# DPPXHK_SENSOR.net
KiCad netlist of a schematic drawn in Altium Designer
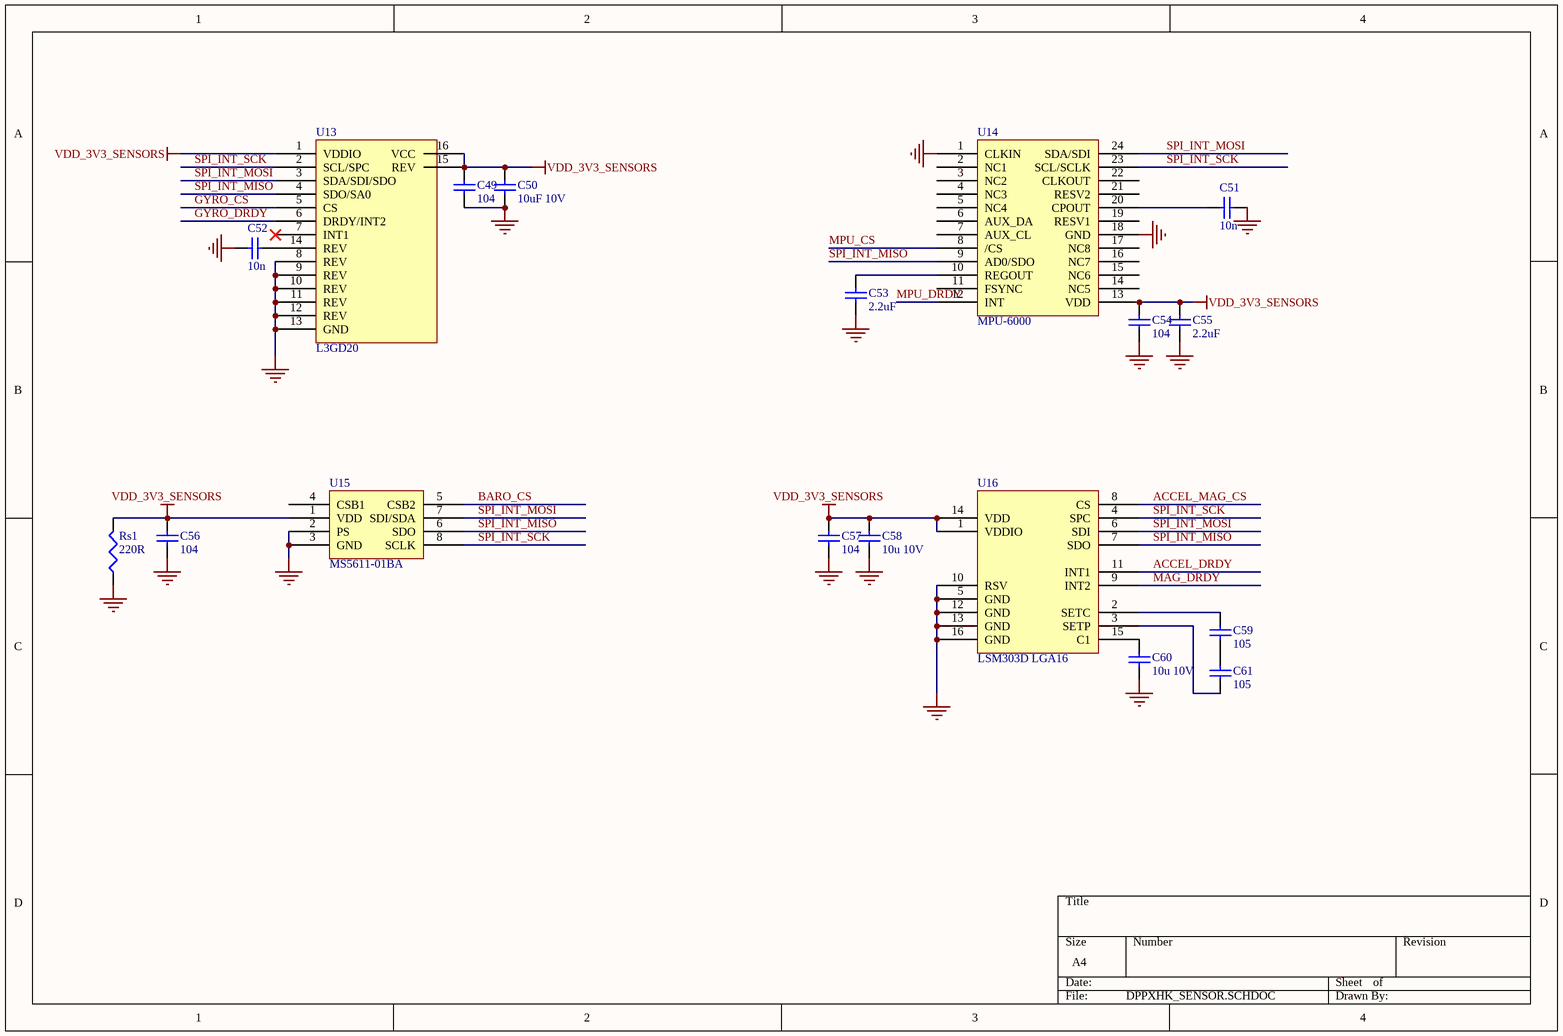
[diagram p0: DPPXHK_SENSOR.SCHDOC]

(export (version "E")
  (design (tool "Eeschema 10.0.6"))
  (components
    (comp (ref "C49")
      (value "104")
      (footprint "LC0402")
      (description "Capacitor (Semiconductor SIM Model)")
      (fields (field (name "PUBLISHER") "Altium Limited"))
      (libsource (lib "Miscellaneous Devices") (part "Cap Semi"))
    )
    (comp (ref "C50")
      (value "10uF 10V")
      (footprint "LC0402")
      (description "Capacitor (Semiconductor SIM Model)")
      (fields (field (name "PUBLISHER") "Altium Limited"))
      (libsource (lib "Miscellaneous Devices") (part "Cap Semi"))
    )
    (comp (ref "C51")
      (value "10n")
      (footprint "LC0402")
      (description "Capacitor (Semiconductor SIM Model)")
      (fields (field (name "PUBLISHER") "Altium Limited"))
      (libsource (lib "Miscellaneous Devices") (part "Cap Semi"))
    )
    (comp (ref "C52")
      (value "10n")
      (footprint "LC0402")
      (description "Capacitor (Semiconductor SIM Model)")
      (fields (field (name "PUBLISHER") "Altium Limited"))
      (libsource (lib "Miscellaneous Devices") (part "Cap Semi"))
    )
    (comp (ref "C53")
      (value "2.2uF")
      (footprint "LC0402")
      (description "Capacitor (Semiconductor SIM Model)")
      (fields (field (name "PUBLISHER") "Altium Limited"))
      (libsource (lib "Miscellaneous Devices") (part "Cap Semi"))
    )
    (comp (ref "C54")
      (value "104")
      (footprint "LC0402")
      (description "Capacitor (Semiconductor SIM Model)")
      (fields (field (name "PUBLISHER") "Altium Limited"))
      (libsource (lib "Miscellaneous Devices") (part "Cap Semi"))
    )
    (comp (ref "C55")
      (value "2.2uF")
      (footprint "LC0402")
      (description "Capacitor (Semiconductor SIM Model)")
      (fields (field (name "PUBLISHER") "Altium Limited"))
      (libsource (lib "Miscellaneous Devices") (part "Cap Semi"))
    )
    (comp (ref "C56")
      (value "104")
      (footprint "LC0402")
      (description "Capacitor (Semiconductor SIM Model)")
      (fields (field (name "PUBLISHER") "Altium Limited"))
      (libsource (lib "Miscellaneous Devices") (part "Cap Semi"))
    )
    (comp (ref "C57")
      (value "104")
      (footprint "LC0402")
      (description "Capacitor (Semiconductor SIM Model)")
      (fields (field (name "PUBLISHER") "Altium Limited"))
      (libsource (lib "Miscellaneous Devices") (part "Cap Semi"))
    )
    (comp (ref "C58")
      (value "10u 10V")
      (footprint "LC0402")
      (description "Capacitor (Semiconductor SIM Model)")
      (fields (field (name "PUBLISHER") "Altium Limited"))
      (libsource (lib "Miscellaneous Devices") (part "Cap Semi"))
    )
    (comp (ref "C59")
      (value "105")
      (footprint "LC0402")
      (description "Capacitor (Semiconductor SIM Model)")
      (fields (field (name "PUBLISHER") "Altium Limited"))
      (libsource (lib "Miscellaneous Devices") (part "Cap Semi"))
    )
    (comp (ref "C60")
      (value "10u 10V")
      (footprint "LC0402")
      (description "Capacitor (Semiconductor SIM Model)")
      (fields (field (name "PUBLISHER") "Altium Limited"))
      (libsource (lib "Miscellaneous Devices") (part "Cap Semi"))
    )
    (comp (ref "C61")
      (value "105")
      (footprint "LC0402")
      (description "Capacitor (Semiconductor SIM Model)")
      (fields (field (name "PUBLISHER") "Altium Limited"))
      (libsource (lib "Miscellaneous Devices") (part "Cap Semi"))
    )
    (comp (ref "Rs1")
      (value "220R")
      (footprint "0402R")
      (description "Resistor")
      (fields (field (name "PUBLISHER") "Altium Limited"))
      (libsource (lib "Miscellaneous Devices") (part "Res3"))
    )
    (comp (ref "U13") (value "L3GD20") (footprint "LGA_16") (libsource (lib "PXHK") (part "L3GD20")))
    (comp (ref "U14") (value "MPU-6000") (footprint "MPU_FP") (libsource (lib "PXHK") (part "MPU-6000")))
    (comp (ref "U15")
      (value "MS5611-01BA")
      (footprint "MS5611-01")
      (libsource (lib "PXHK") (part "MS5611-01BA"))
    )
    (comp (ref "U16")
      (value "LSM303D LGA16")
      (footprint "LGA_3_3_16L")
      (libsource (lib "PXHK") (part "LSM303D LGA16"))
    )
  )
  (nets
    (net (code "1") (name "/ACCEL_DRDY") (class "Default")
      (node (ref "U16") (pin "11") (pinfunction "INT1_11") (pintype "passive"))
    )
    (net (code "2") (name "/ACCEL_MAG_CS") (class "Default")
      (node (ref "U16") (pin "8") (pinfunction "CS_8") (pintype "passive"))
    )
    (net (code "3") (name "/BARO_CS") (class "Default")
      (node (ref "U15") (pin "5") (pinfunction "CSB2_5") (pintype "passive"))
    )
    (net (code "4") (name "/GYRO_CS") (class "Default")
      (node (ref "U13") (pin "5") (pinfunction "CS_5") (pintype "passive"))
    )
    (net (code "5") (name "/GYRO_DRDY") (class "Default")
      (node (ref "U13") (pin "6") (pinfunction "DRDY/INT2_6") (pintype "passive"))
    )
    (net (code "6") (name "/MAG_DRDY") (class "Default")
      (node (ref "U16") (pin "9") (pinfunction "INT2_9") (pintype "passive"))
    )
    (net (code "7") (name "/MPU_CS") (class "Default")
      (node (ref "U14") (pin "8") (pinfunction "/CS_8") (pintype "passive"))
    )
    (net (code "8") (name "/MPU_DRDY") (class "Default")
      (node (ref "U14") (pin "12") (pinfunction "INT_12") (pintype "passive"))
    )
    (net (code "9") (name "/SPI_INT_MISO") (class "Default")
      (node (ref "U13") (pin "4") (pinfunction "SDO/SA0_4") (pintype "passive"))
      (node (ref "U14") (pin "9") (pinfunction "AD0/SDO_9") (pintype "passive"))
      (node (ref "U15") (pin "6") (pinfunction "SDO_6") (pintype "passive"))
      (node (ref "U16") (pin "7") (pinfunction "SDO_7") (pintype "passive"))
    )
    (net (code "10") (name "/SPI_INT_MOSI") (class "Default")
      (node (ref "U13") (pin "3") (pinfunction "SDA/SDI/SDO_3") (pintype "passive"))
      (node (ref "U14") (pin "24") (pinfunction "SDA/SDI_24") (pintype "passive"))
      (node (ref "U15") (pin "7") (pinfunction "SDI/SDA_7") (pintype "passive"))
      (node (ref "U16") (pin "6") (pinfunction "SDI_6") (pintype "passive"))
    )
    (net (code "11") (name "/SPI_INT_SCK") (class "Default")
      (node (ref "U13") (pin "2") (pinfunction "SCL/SPC_2") (pintype "passive"))
      (node (ref "U14") (pin "23") (pinfunction "SCL/SCLK_23") (pintype "passive"))
      (node (ref "U15") (pin "8") (pinfunction "SCLK_8") (pintype "passive"))
      (node (ref "U16") (pin "4") (pinfunction "SPC_4") (pintype "passive"))
    )
    (net (code "12") (name "GND") (class "Default")
      (node (ref "C49") (pin "1") (pinfunction "1_1") (pintype "passive"))
      (node (ref "C50") (pin "1") (pinfunction "1_1") (pintype "passive"))
      (node (ref "C51") (pin "1") (pinfunction "1_1") (pintype "passive"))
      (node (ref "C52") (pin "1") (pinfunction "1_1") (pintype "passive"))
      (node (ref "C53") (pin "1") (pinfunction "1_1") (pintype "passive"))
      (node (ref "C54") (pin "1") (pinfunction "1_1") (pintype "passive"))
      (node (ref "C55") (pin "1") (pinfunction "1_1") (pintype "passive"))
      (node (ref "C56") (pin "1") (pinfunction "1_1") (pintype "passive"))
      (node (ref "C57") (pin "1") (pinfunction "1_1") (pintype "passive"))
      (node (ref "C58") (pin "1") (pinfunction "1_1") (pintype "passive"))
      (node (ref "C60") (pin "1") (pinfunction "1_1") (pintype "passive"))
      (node (ref "Rs1") (pin "1") (pinfunction "1_1") (pintype "passive"))
      (node (ref "U13") (pin "10") (pinfunction "REV_10") (pintype "passive"))
      (node (ref "U13") (pin "11") (pinfunction "REV_11") (pintype "passive"))
      (node (ref "U13") (pin "12") (pinfunction "REV_12") (pintype "passive"))
      (node (ref "U13") (pin "13") (pinfunction "GND_13") (pintype "passive"))
      (node (ref "U13") (pin "8") (pinfunction "REV_8") (pintype "passive"))
      (node (ref "U13") (pin "9") (pinfunction "REV_9") (pintype "passive"))
      (node (ref "U14") (pin "1") (pinfunction "CLKIN_1") (pintype "passive"))
      (node (ref "U14") (pin "18") (pinfunction "GND_18") (pintype "passive"))
      (node (ref "U15") (pin "2") (pinfunction "PS_2") (pintype "passive"))
      (node (ref "U15") (pin "3") (pinfunction "GND_3") (pintype "passive"))
      (node (ref "U16") (pin "10") (pinfunction "RSV_10") (pintype "passive"))
      (node (ref "U16") (pin "12") (pinfunction "GND_12") (pintype "passive"))
      (node (ref "U16") (pin "13") (pinfunction "GND_13") (pintype "passive"))
      (node (ref "U16") (pin "16") (pinfunction "GND_16") (pintype "passive"))
      (node (ref "U16") (pin "5") (pinfunction "GND_5") (pintype "passive"))
    )
    (net (code "13") (name "Net-(C52-Pad2)") (class "Default")
      (node (ref "C52") (pin "2") (pinfunction "2_2") (pintype "passive"))
      (node (ref "U13") (pin "14") (pinfunction "REV_14") (pintype "passive"))
    )
    (net (code "14") (name "Net-(C59-Pad1)") (class "Default")
      (node (ref "C59") (pin "1") (pinfunction "1_1") (pintype "passive"))
      (node (ref "C61") (pin "2") (pinfunction "2_2") (pintype "passive"))
    )
    (net (code "15") (name "Net-(U14-CPOUT)") (class "Default")
      (node (ref "C51") (pin "2") (pinfunction "2_2") (pintype "passive"))
      (node (ref "U14") (pin "20") (pinfunction "CPOUT_20") (pintype "passive"))
    )
    (net (code "16") (name "Net-(U14-REGOUT)") (class "Default")
      (node (ref "C53") (pin "2") (pinfunction "2_2") (pintype "passive"))
      (node (ref "U14") (pin "10") (pinfunction "REGOUT_10") (pintype "passive"))
    )
    (net (code "17") (name "Net-(U16-C1)") (class "Default")
      (node (ref "C60") (pin "2") (pinfunction "2_2") (pintype "passive"))
      (node (ref "U16") (pin "15") (pinfunction "C1_15") (pintype "passive"))
    )
    (net (code "18") (name "Net-(U16-SETC)") (class "Default")
      (node (ref "C59") (pin "2") (pinfunction "2_2") (pintype "passive"))
      (node (ref "U16") (pin "2") (pinfunction "SETC_2") (pintype "passive"))
    )
    (net (code "19") (name "Net-(U16-SETP)") (class "Default")
      (node (ref "C61") (pin "1") (pinfunction "1_1") (pintype "passive"))
      (node (ref "U16") (pin "3") (pinfunction "SETP_3") (pintype "passive"))
    )
    (net (code "20") (name "VDD_3V3_SENSORS") (class "Default")
      (node (ref "C49") (pin "2") (pinfunction "2_2") (pintype "passive"))
      (node (ref "C50") (pin "2") (pinfunction "2_2") (pintype "passive"))
      (node (ref "C54") (pin "2") (pinfunction "2_2") (pintype "passive"))
      (node (ref "C55") (pin "2") (pinfunction "2_2") (pintype "passive"))
      (node (ref "C56") (pin "2") (pinfunction "2_2") (pintype "passive"))
      (node (ref "C57") (pin "2") (pinfunction "2_2") (pintype "passive"))
      (node (ref "C58") (pin "2") (pinfunction "2_2") (pintype "passive"))
      (node (ref "Rs1") (pin "2") (pinfunction "2_2") (pintype "passive"))
      (node (ref "U13") (pin "1") (pinfunction "VDDIO_1") (pintype "passive"))
      (node (ref "U13") (pin "15") (pinfunction "REV_15") (pintype "passive"))
      (node (ref "U13") (pin "16") (pinfunction "VCC_16") (pintype "passive"))
      (node (ref "U14") (pin "13") (pinfunction "VDD_13") (pintype "passive"))
      (node (ref "U15") (pin "1") (pinfunction "VDD_1") (pintype "passive"))
      (node (ref "U16") (pin "1") (pinfunction "VDDIO_1") (pintype "passive"))
      (node (ref "U16") (pin "14") (pinfunction "VDD_14") (pintype "passive"))
    )
    (net (code "21") (name "unconnected-(U13-INT1-Pad7)") (class "Default")
      (node (ref "U13") (pin "7") (pinfunction "INT1_7") (pintype "passive+no_connect"))
    )
    (net (code "22") (name "unconnected-(U14-AUX_CL-Pad7)") (class "Default")
      (node (ref "U14") (pin "7") (pinfunction "AUX_CL_7") (pintype "passive"))
    )
    (net (code "23") (name "unconnected-(U14-AUX_DA-Pad6)") (class "Default")
      (node (ref "U14") (pin "6") (pinfunction "AUX_DA_6") (pintype "passive"))
    )
    (net (code "24") (name "unconnected-(U14-CLKOUT-Pad22)") (class "Default")
      (node (ref "U14") (pin "22") (pinfunction "CLKOUT_22") (pintype "passive"))
    )
    (net (code "25") (name "unconnected-(U14-FSYNC-Pad11)") (class "Default")
      (node (ref "U14") (pin "11") (pinfunction "FSYNC_11") (pintype "passive"))
    )
    (net (code "26") (name "unconnected-(U14-NC1-Pad2)") (class "Default")
      (node (ref "U14") (pin "2") (pinfunction "NC1_2") (pintype "passive"))
    )
    (net (code "27") (name "unconnected-(U14-NC2-Pad3)") (class "Default")
      (node (ref "U14") (pin "3") (pinfunction "NC2_3") (pintype "passive"))
    )
    (net (code "28") (name "unconnected-(U14-NC3-Pad4)") (class "Default")
      (node (ref "U14") (pin "4") (pinfunction "NC3_4") (pintype "passive"))
    )
    (net (code "29") (name "unconnected-(U14-NC4-Pad5)") (class "Default")
      (node (ref "U14") (pin "5") (pinfunction "NC4_5") (pintype "passive"))
    )
    (net (code "30") (name "unconnected-(U14-NC5-Pad14)") (class "Default")
      (node (ref "U14") (pin "14") (pinfunction "NC5_14") (pintype "passive"))
    )
    (net (code "31") (name "unconnected-(U14-NC6-Pad15)") (class "Default")
      (node (ref "U14") (pin "15") (pinfunction "NC6_15") (pintype "passive"))
    )
    (net (code "32") (name "unconnected-(U14-NC7-Pad16)") (class "Default")
      (node (ref "U14") (pin "16") (pinfunction "NC7_16") (pintype "passive"))
    )
    (net (code "33") (name "unconnected-(U14-NC8-Pad17)") (class "Default")
      (node (ref "U14") (pin "17") (pinfunction "NC8_17") (pintype "passive"))
    )
    (net (code "34") (name "unconnected-(U14-RESV1-Pad19)") (class "Default")
      (node (ref "U14") (pin "19") (pinfunction "RESV1_19") (pintype "passive"))
    )
    (net (code "35") (name "unconnected-(U14-RESV2-Pad21)") (class "Default")
      (node (ref "U14") (pin "21") (pinfunction "RESV2_21") (pintype "passive"))
    )
    (net (code "36") (name "unconnected-(U15-CSB1-Pad4)") (class "Default")
      (node (ref "U15") (pin "4") (pinfunction "CSB1_4") (pintype "passive"))
    )
  )
)
